# Sheet1.net
KiCad netlist of a schematic drawn in Altium Designer
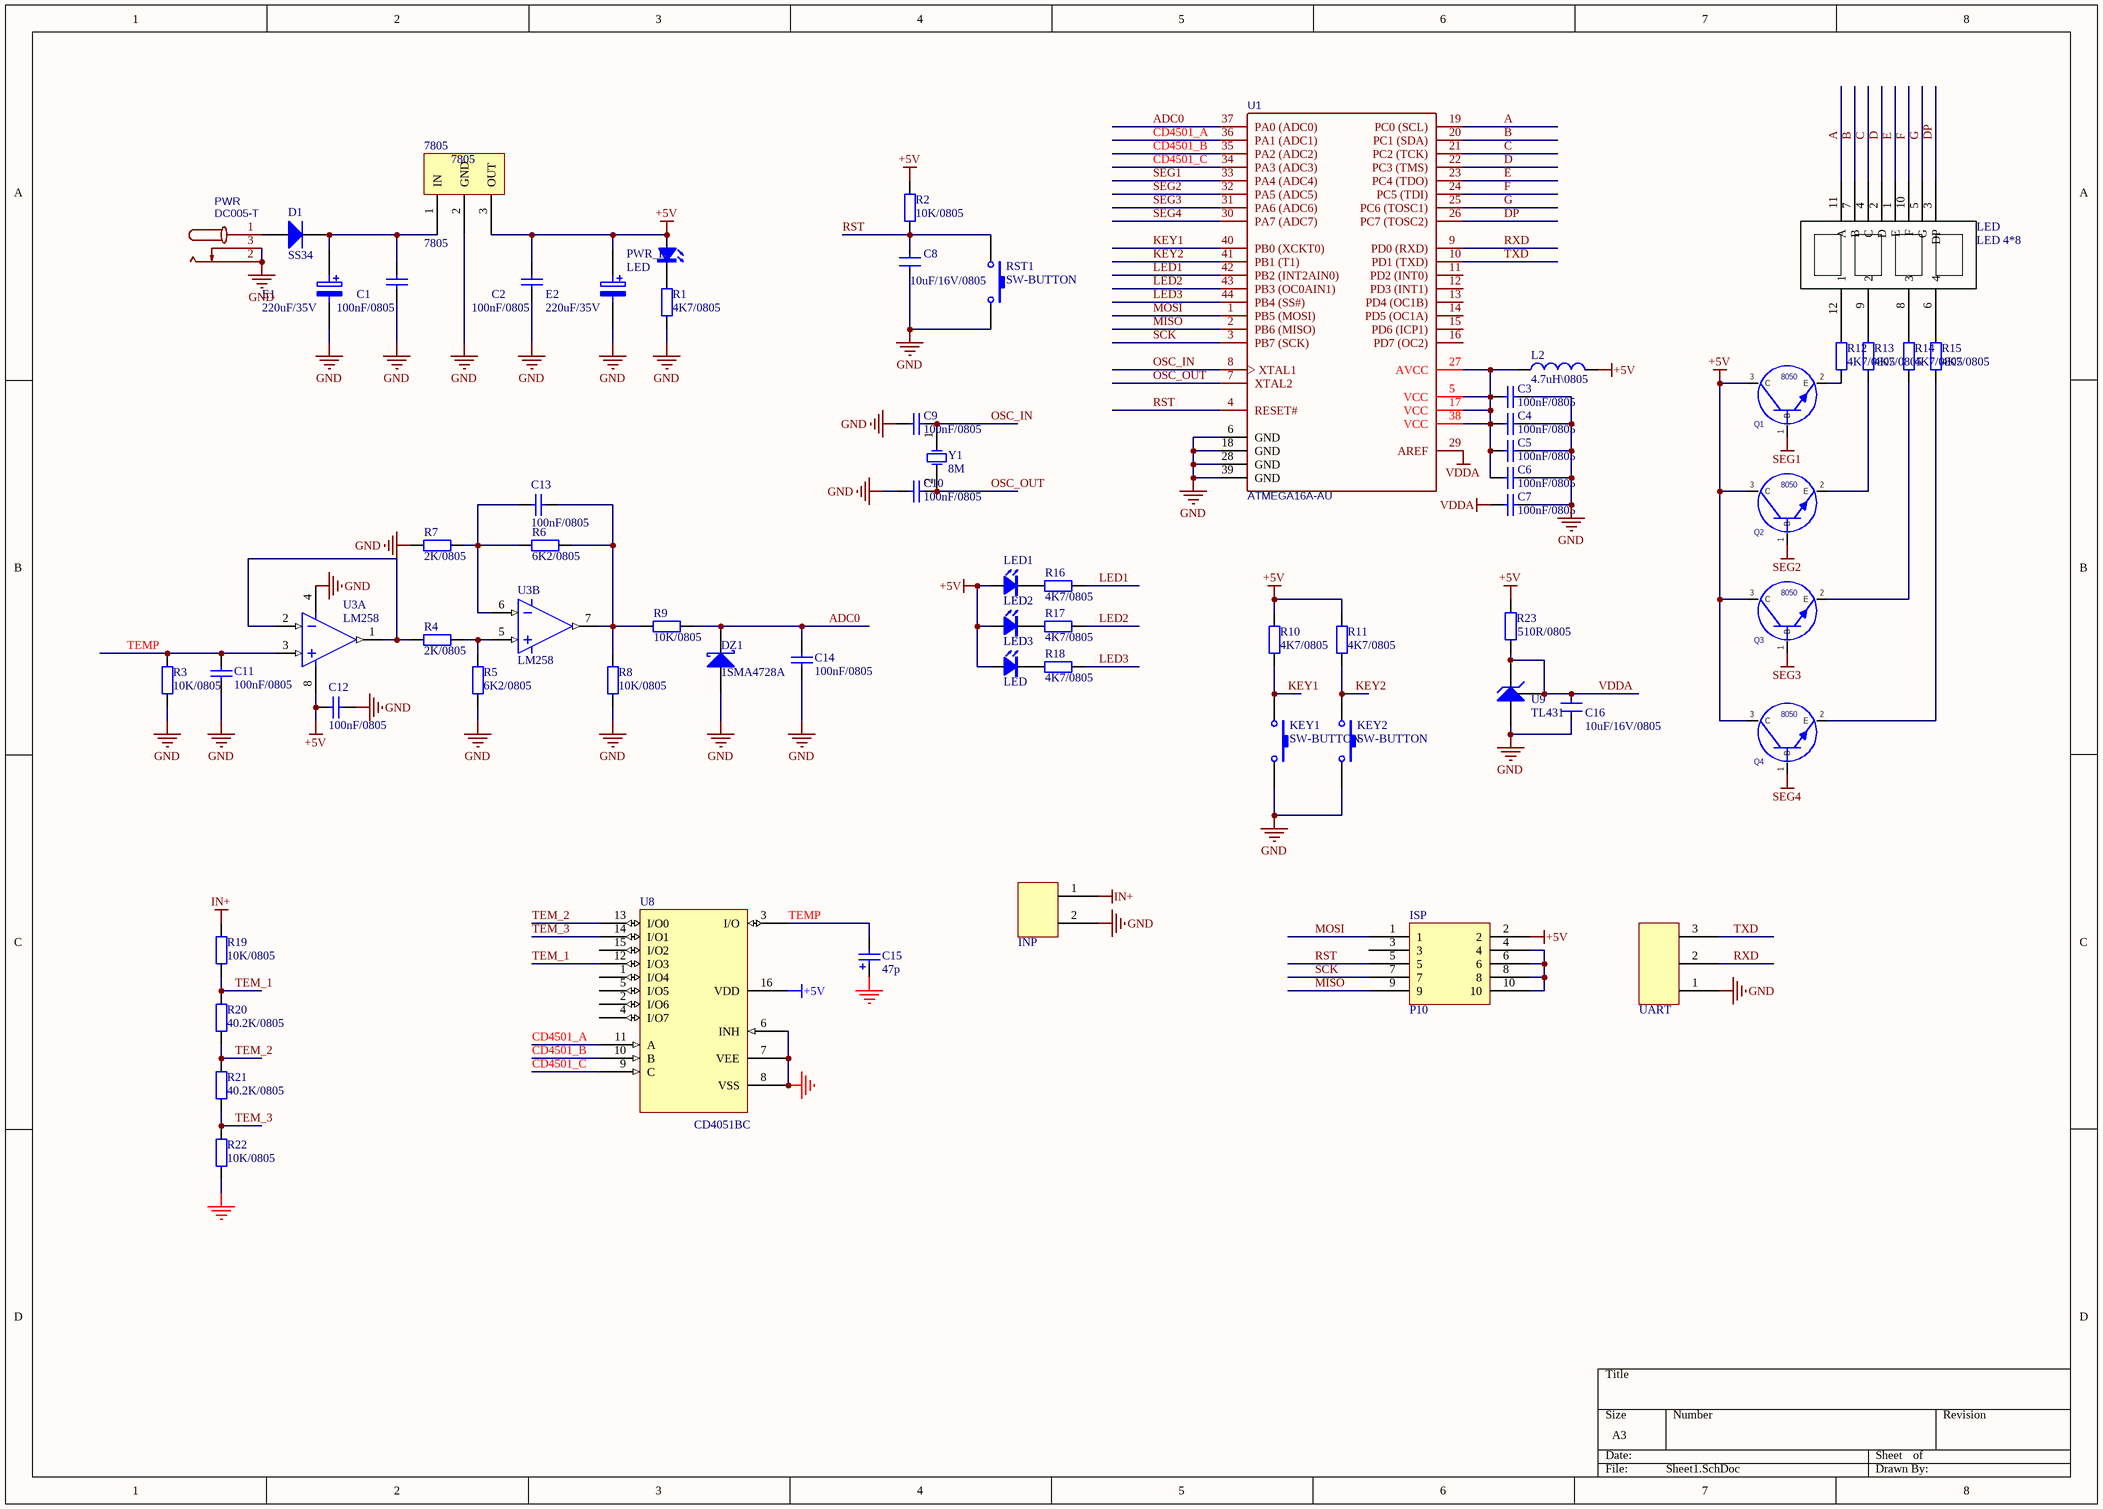
[diagram p0: Sheet1.SchDoc]

(export (version "E")
  (design (tool "Eeschema 10.0.6"))
  (components
    (comp (ref "7805") (value "7805") (footprint "7805") (libsource (lib "Schl_lib") (part "7805")))
    (comp (ref "C1")
      (value "100nF/0805")
      (footprint "C0805")
      (description "Capacitor (Semiconductor SIM Model)")
      (fields (field (name "PUBLISHER") "Altium Limited"))
      (libsource (lib "*") (part "Cap Semi"))
    )
    (comp (ref "C2")
      (value "100nF/0805")
      (footprint "C0805")
      (description "Capacitor (Semiconductor SIM Model)")
      (fields (field (name "PUBLISHER") "Altium Limited"))
      (libsource (lib "*") (part "Cap Semi"))
    )
    (comp (ref "C3")
      (value "100nF/0805")
      (footprint "C0805")
      (description "Capacitor (Semiconductor SIM Model)")
      (fields (field (name "PUBLISHER") "Altium Limited"))
      (libsource (lib "*") (part "Cap Semi"))
    )
    (comp (ref "C4")
      (value "100nF/0805")
      (footprint "C0805")
      (description "Capacitor (Semiconductor SIM Model)")
      (fields (field (name "PUBLISHER") "Altium Limited"))
      (libsource (lib "*") (part "Cap Semi"))
    )
    (comp (ref "C5")
      (value "100nF/0805")
      (footprint "C0805")
      (description "Capacitor (Semiconductor SIM Model)")
      (fields (field (name "PUBLISHER") "Altium Limited"))
      (libsource (lib "*") (part "Cap Semi"))
    )
    (comp (ref "C6")
      (value "100nF/0805")
      (footprint "C0805")
      (description "Capacitor (Semiconductor SIM Model)")
      (fields (field (name "PUBLISHER") "Altium Limited"))
      (libsource (lib "*") (part "Cap Semi"))
    )
    (comp (ref "C7")
      (value "100nF/0805")
      (footprint "C0805")
      (description "Capacitor (Semiconductor SIM Model)")
      (fields (field (name "PUBLISHER") "Altium Limited"))
      (libsource (lib "*") (part "Cap Semi"))
    )
    (comp (ref "C8")
      (value "10uF")
      (footprint "C0805")
      (description "普通小电容")
      (fields (field (name "MARK") "10uF/16V/0805"))
      (libsource (lib "MOTO_CTRL") (part "CAP"))
    )
    (comp (ref "C9")
      (value "100nF/0805")
      (footprint "C0805")
      (description "Capacitor (Semiconductor SIM Model)")
      (fields (field (name "PUBLISHER") "Altium Limited"))
      (libsource (lib "*") (part "Cap Semi"))
    )
    (comp (ref "C10")
      (value "100nF/0805")
      (footprint "C0805")
      (description "Capacitor (Semiconductor SIM Model)")
      (fields (field (name "PUBLISHER") "Altium Limited"))
      (libsource (lib "*") (part "Cap Semi"))
    )
    (comp (ref "C11")
      (value "100nF/0805")
      (footprint "C0805")
      (description "Capacitor (Semiconductor SIM Model)")
      (fields (field (name "PUBLISHER") "Altium Limited"))
      (libsource (lib "*") (part "Cap Semi"))
    )
    (comp (ref "C12")
      (value "100nF/0805")
      (footprint "C0805")
      (description "Capacitor (Semiconductor SIM Model)")
      (fields (field (name "PUBLISHER") "Altium Limited"))
      (libsource (lib "*") (part "Cap Semi"))
    )
    (comp (ref "C13")
      (value "100nF/0805")
      (footprint "C0805")
      (description "Capacitor (Semiconductor SIM Model)")
      (fields (field (name "PUBLISHER") "Altium Limited"))
      (libsource (lib "*") (part "Cap Semi"))
    )
    (comp (ref "C14")
      (value "100nF/0805")
      (footprint "C0805")
      (description "Capacitor (Semiconductor SIM Model)")
      (fields (field (name "PUBLISHER") "Altium Limited"))
      (libsource (lib "*") (part "Cap Semi"))
    )
    (comp (ref "C15")
      (value "47p")
      (footprint "C0805")
      (description "Polarized Capacitor (Radial)")
      (fields
        (field (name "MANUFACTURER") "Generic Components")
        (field (name "PUBLISHER") "Altium Hobart Technology Centre")
      )
      (libsource (lib "Miscellaneous Devices") (part "Cap Pol1"))
    )
    (comp (ref "C16")
      (value "10uF")
      (footprint "C0805")
      (description "普通小电容")
      (fields (field (name "MARK") "10uF/16V/0805"))
      (libsource (lib "SCH_Lib") (part "CAP"))
    )
    (comp (ref "D1")
      (value "SS34")
      (footprint "PCB_LIB:SMA")
      (description "High Conductance Fast Diode")
      (fields (field (name "PUBLISHER") "Altium Limited"))
      (libsource (lib "*") (part "Diode 1N914"))
    )
    (comp (ref "DZ1")
      (value "1SMA4728A")
      (footprint "PCB_LIB:SMA")
      (description "Schottky Rectifier")
      (fields (field (name "MARK") "1SMA4728A"))
      (libsource (lib "Schl_lib") (part "DZ"))
    )
    (comp (ref "E1")
      (value "220uF/35V")
      (footprint "CAP-8*10.5MM/CDVT")
      (description "Electrolytic Capacitor")
      (libsource (lib "*") (part "ELECTRO2"))
    )
    (comp (ref "E2")
      (value "220uF/35V")
      (footprint "CAP-8*10.5MM/CDVT")
      (description "Electrolytic Capacitor")
      (libsource (lib "*") (part "ELECTRO2"))
    )
    (comp (ref "INP") (value "P") (footprint "POWER2") (libsource (lib "Schl_lib") (part "P2")))
    (comp (ref "ISP") (value "P10") (footprint "IDC-10P") (libsource (lib "Schl_lib") (part "P10")))
    (comp (ref "KEY1")
      (value "SW-BUTTON")
      (footprint "KEY-SMD_4P-6-6")
      (description "6*6*5mm轻触开关")
      (libsource (lib "STC52_CAD") (part "SW-BUTTON"))
    )
    (comp (ref "KEY2")
      (value "SW-BUTTON")
      (footprint "KEY-SMD_4P-6-6")
      (description "6*6*5mm轻触开关")
      (libsource (lib "STC52_CAD") (part "SW-BUTTON"))
    )
    (comp (ref "L2")
      (value "Inductor")
      (footprint "0805L")
      (fields (field (name "MARK") "4.7u~{H}0805") (field (name "PUBLISHER") "Altium Limited"))
      (libsource (lib "Miscellaneous Devices") (part "Inductor"))
    )
    (comp (ref "LED")
      (value "LED 4*8")
      (footprint "DIGITAL_LED_0.56")
      (libsource (lib "Schl_lib") (part "LED4*8"))
    )
    (comp (ref "LED1") (value "LED") (footprint "LED0805") (libsource (lib "SCH_Lib") (part "LED")))
    (comp (ref "LED2") (value "LED") (footprint "LED0805") (libsource (lib "SCH_Lib") (part "LED")))
    (comp (ref "LED3") (value "LED") (footprint "LED0805") (libsource (lib "SCH_Lib") (part "LED")))
    (comp (ref "PWR")
      (value "DC005-T")
      (footprint "DC005")
      (fields (field (name "BOM_SUPPLIER PART") "C431532") (field (name "CONTRIBUTOR") "LCSC"))
      (libsource (lib "altium-import") (part "root_0_DC005-T_"))
    )
    (comp (ref "PWR_L") (value "LED") (footprint "LED0805") (libsource (lib "") (part "LED_1")))
    (comp (ref "Q1")
      (value "8050")
      (footprint "SOT-23")
      (description "Transistor;NPN;40V;200mA;SOT23;1.1mm;ROHS")
      (libsource (lib "*") (part "TRIODE-NPN-MMBT3904"))
    )
    (comp (ref "Q2")
      (value "8050")
      (footprint "SOT-23")
      (description "Transistor;NPN;40V;200mA;SOT23;1.1mm;ROHS")
      (libsource (lib "*") (part "TRIODE-NPN-MMBT3904"))
    )
    (comp (ref "Q3")
      (value "8050")
      (footprint "SOT-23")
      (description "Transistor;NPN;40V;200mA;SOT23;1.1mm;ROHS")
      (libsource (lib "*") (part "TRIODE-NPN-MMBT3904"))
    )
    (comp (ref "Q4")
      (value "8050")
      (footprint "SOT-23")
      (description "Transistor;NPN;40V;200mA;SOT23;1.1mm;ROHS")
      (libsource (lib "*") (part "TRIODE-NPN-MMBT3904"))
    )
    (comp (ref "R1")
      (value "4K7/0805")
      (footprint "R0805")
      (description "Resistor")
      (fields (field (name "MARK") "4K7/0805") (field (name "PUBLISHER") "Altium Limited"))
      (libsource (lib "SCH_Lib") (part "RES"))
    )
    (comp (ref "R2")
      (value "10K")
      (footprint "R0805")
      (description "Resistor")
      (fields (field (name "MARK") "10K/0805") (field (name "PUBLISHER") "Altium Limited"))
      (libsource (lib "MOTO_CTRL") (part "RES"))
    )
    (comp (ref "R3")
      (value "10K")
      (footprint "R0805")
      (description "Resistor")
      (fields (field (name "MARK") "10K/0805") (field (name "PUBLISHER") "Altium Limited"))
      (libsource (lib "MOTO_CTRL") (part "RES"))
    )
    (comp (ref "R4")
      (value "2K/0805")
      (footprint "R0805")
      (description "Resistor")
      (fields (field (name "MARK") "2K/0805") (field (name "PUBLISHER") "Altium Limited"))
      (libsource (lib "") (part "RES_1"))
    )
    (comp (ref "R5")
      (value "6K2/0805")
      (footprint "R0805")
      (description "Resistor")
      (fields (field (name "MARK") "6K2/0805") (field (name "PUBLISHER") "Altium Limited"))
      (libsource (lib "") (part "RES_2"))
    )
    (comp (ref "R6")
      (value "6K2/0805")
      (footprint "R0805")
      (description "Resistor")
      (fields (field (name "MARK") "6K2/0805") (field (name "PUBLISHER") "Altium Limited"))
      (libsource (lib "") (part "RES_3"))
    )
    (comp (ref "R7")
      (value "2K/0805")
      (footprint "R0805")
      (description "Resistor")
      (fields (field (name "MARK") "2K/0805") (field (name "PUBLISHER") "Altium Limited"))
      (libsource (lib "") (part "RES_3"))
    )
    (comp (ref "R8")
      (value "10K/0805")
      (footprint "R0805")
      (description "Resistor")
      (fields (field (name "MARK") "10K/0805") (field (name "PUBLISHER") "Altium Limited"))
      (libsource (lib "SCH_Lib") (part "RES"))
    )
    (comp (ref "R9")
      (value "10K/0805")
      (footprint "R0805")
      (description "Resistor")
      (fields (field (name "MARK") "10K/0805") (field (name "PUBLISHER") "Altium Limited"))
      (libsource (lib "") (part "RES_1"))
    )
    (comp (ref "R10")
      (value "4K7/0805")
      (footprint "R0805")
      (description "Resistor")
      (fields (field (name "MARK") "4K7/0805") (field (name "PUBLISHER") "Altium Limited"))
      (libsource (lib "") (part "RES_2"))
    )
    (comp (ref "R11")
      (value "4K7/0805")
      (footprint "R0805")
      (description "Resistor")
      (fields (field (name "MARK") "4K7/0805") (field (name "PUBLISHER") "Altium Limited"))
      (libsource (lib "") (part "RES_2"))
    )
    (comp (ref "R12")
      (value "4K7/0805")
      (footprint "R0805")
      (description "Resistor")
      (fields (field (name "MARK") "4K7/0805") (field (name "PUBLISHER") "Altium Limited"))
      (libsource (lib "") (part "RES_2"))
    )
    (comp (ref "R13")
      (value "4K7/0805")
      (footprint "R0805")
      (description "Resistor")
      (fields (field (name "MARK") "4K7/0805") (field (name "PUBLISHER") "Altium Limited"))
      (libsource (lib "") (part "RES_2"))
    )
    (comp (ref "R14")
      (value "4K7/0805")
      (footprint "R0805")
      (description "Resistor")
      (fields (field (name "MARK") "4K7/0805") (field (name "PUBLISHER") "Altium Limited"))
      (libsource (lib "") (part "RES_2"))
    )
    (comp (ref "R15")
      (value "4K7/0805")
      (footprint "R0805")
      (description "Resistor")
      (fields (field (name "MARK") "4K7/0805") (field (name "PUBLISHER") "Altium Limited"))
      (libsource (lib "") (part "RES_2"))
    )
    (comp (ref "R16")
      (value "4K7/0805")
      (footprint "R0805")
      (description "Resistor")
      (fields (field (name "MARK") "4K7/0805") (field (name "PUBLISHER") "Altium Limited"))
      (libsource (lib "") (part "RES_1"))
    )
    (comp (ref "R17")
      (value "4K7/0805")
      (footprint "R0805")
      (description "Resistor")
      (fields (field (name "MARK") "4K7/0805") (field (name "PUBLISHER") "Altium Limited"))
      (libsource (lib "") (part "RES_1"))
    )
    (comp (ref "R18")
      (value "4K7/0805")
      (footprint "R0805")
      (description "Resistor")
      (fields (field (name "MARK") "4K7/0805") (field (name "PUBLISHER") "Altium Limited"))
      (libsource (lib "") (part "RES_1"))
    )
    (comp (ref "R19")
      (value "10K/0805")
      (footprint "R0805")
      (description "Resistor")
      (fields (field (name "MARK") "10K/0805") (field (name "PUBLISHER") "Altium Limited"))
      (libsource (lib "") (part "RES_2"))
    )
    (comp (ref "R20")
      (value "40.2K/0805")
      (footprint "R0805")
      (description "Resistor")
      (fields (field (name "MARK") "40.2K/0805") (field (name "PUBLISHER") "Altium Limited"))
      (libsource (lib "") (part "RES_2"))
    )
    (comp (ref "R21")
      (value "40.2K/0805")
      (footprint "R0805")
      (description "Resistor")
      (fields (field (name "MARK") "40.2K/0805") (field (name "PUBLISHER") "Altium Limited"))
      (libsource (lib "") (part "RES_2"))
    )
    (comp (ref "R22")
      (value "10K/0805")
      (footprint "R0805")
      (description "Resistor")
      (fields (field (name "MARK") "10K/0805") (field (name "PUBLISHER") "Altium Limited"))
      (libsource (lib "") (part "RES_2"))
    )
    (comp (ref "R23")
      (value "510R")
      (footprint "R0805")
      (description "Resistor")
      (fields (field (name "MARK") "510R/0805") (field (name "PUBLISHER") "Altium Limited"))
      (libsource (lib "") (part "RES_2"))
    )
    (comp (ref "RST1")
      (value "SW-BUTTON")
      (footprint "KEY-SMD_4P-6-6")
      (description "6*6*5mm轻触开关")
      (libsource (lib "STC52_CAD") (part "SW-BUTTON"))
    )
    (comp (ref "U1")
      (value "ATMEGA16A-AU")
      (footprint "TQFP-44")
      (fields (field (name "BOM_SUPPLIER PART") "C5658"))
      (libsource (lib "Schl_lib") (part "ATMEGA16A-AU"))
    )
    (comp (ref "U3")
      (value "LM258")
      (footprint "SO-8")
      (description "电压比较器")
      (libsource (lib "SCH_Lib") (part "LM393"))
    )
    (comp (ref "U8") (value "CD4051BC") (footprint "SO-16") (libsource (lib "*") (part "CD4051BC")))
    (comp (ref "U9")
      (value "TL431")
      (footprint "TL431")
      (fields (field (name "MARK") "TL431") (field (name "PUBLISHER") "Altium Limited"))
      (libsource (lib "Schl_lib") (part "TL431"))
    )
    (comp (ref "UART") (value "P") (footprint "POWER3") (libsource (lib "Schl_lib") (part "P3")))
    (comp (ref "Y1")
      (value "8M")
      (footprint "SMD3225")
      (description "Crystal Oscillator")
      (fields (field (name "PUBLISHER") "Altium Limited"))
      (libsource (lib "Miscellaneous Devices") (part "XTAL"))
    )
  )
  (nets
    (net (code "1") (name "+5V") (class "Default")
      (node (ref "7805") (pin "3") (pinfunction "OUT_3") (pintype "passive"))
      (node (ref "C12") (pin "1") (pinfunction "1_1") (pintype "passive"))
      (node (ref "C2") (pin "2") (pinfunction "2_2") (pintype "passive"))
      (node (ref "E2") (pin "1") (pinfunction "1_1") (pintype "passive"))
      (node (ref "ISP") (pin "2") (pinfunction "2_2") (pintype "passive"))
      (node (ref "L2") (pin "2") (pinfunction "2_2") (pintype "passive"))
      (node (ref "LED1") (pin "1") (pinfunction "A_1") (pintype "passive"))
      (node (ref "LED2") (pin "1") (pinfunction "A_1") (pintype "passive"))
      (node (ref "LED3") (pin "1") (pinfunction "A_1") (pintype "passive"))
      (node (ref "PWR_L") (pin "1") (pinfunction "A_1") (pintype "passive"))
      (node (ref "Q1") (pin "3") (pinfunction "C_3") (pintype "passive"))
      (node (ref "Q2") (pin "3") (pinfunction "C_3") (pintype "passive"))
      (node (ref "Q3") (pin "3") (pinfunction "C_3") (pintype "passive"))
      (node (ref "Q4") (pin "3") (pinfunction "C_3") (pintype "passive"))
      (node (ref "R10") (pin "2") (pinfunction "2_2") (pintype "passive"))
      (node (ref "R11") (pin "2") (pinfunction "2_2") (pintype "passive"))
      (node (ref "R2") (pin "2") (pinfunction "2_2") (pintype "passive"))
      (node (ref "R23") (pin "2") (pinfunction "2_2") (pintype "passive"))
      (node (ref "U3") (pin "8") (pinfunction "V+_8") (pintype "power_in"))
      (node (ref "U8") (pin "16") (pinfunction "VDD_16") (pintype "power_in"))
    )
    (net (code "2") (name "/A") (class "Default")
      (node (ref "LED") (pin "11") (pinfunction "A_11") (pintype "passive"))
      (node (ref "U1") (pin "19") (pinfunction "PC0_(SCL)_19") (pintype "passive"))
    )
    (net (code "3") (name "/ADC0") (class "Default")
      (node (ref "C14") (pin "1") (pinfunction "1_1") (pintype "passive"))
      (node (ref "DZ1") (pin "2") (pinfunction "K_2") (pintype "passive"))
      (node (ref "R9") (pin "2") (pinfunction "2_2") (pintype "passive"))
      (node (ref "U1") (pin "37") (pinfunction "PA0_(ADC0)_37") (pintype "passive"))
    )
    (net (code "4") (name "/B") (class "Default")
      (node (ref "LED") (pin "7") (pinfunction "B_7") (pintype "passive"))
      (node (ref "U1") (pin "20") (pinfunction "PC1_(SDA)_20") (pintype "passive"))
    )
    (net (code "5") (name "/C") (class "Default")
      (node (ref "LED") (pin "4") (pinfunction "C_4") (pintype "passive"))
      (node (ref "U1") (pin "21") (pinfunction "PC2_(TCK)_21") (pintype "passive"))
    )
    (net (code "6") (name "/CD4501_A") (class "Default")
      (node (ref "U1") (pin "36") (pinfunction "PA1_(ADC1)_36") (pintype "passive"))
      (node (ref "U8") (pin "11") (pinfunction "A_11") (pintype "input"))
    )
    (net (code "7") (name "/CD4501_B") (class "Default")
      (node (ref "U1") (pin "35") (pinfunction "PA2_(ADC2)_35") (pintype "passive"))
      (node (ref "U8") (pin "10") (pinfunction "B_10") (pintype "input"))
    )
    (net (code "8") (name "/CD4501_C") (class "Default")
      (node (ref "U1") (pin "34") (pinfunction "PA3_(ADC3)_34") (pintype "passive"))
      (node (ref "U8") (pin "9") (pinfunction "C_9") (pintype "input"))
    )
    (net (code "9") (name "/D") (class "Default")
      (node (ref "LED") (pin "2") (pinfunction "D_2") (pintype "passive"))
      (node (ref "U1") (pin "22") (pinfunction "PC3_(TMS)_22") (pintype "passive"))
    )
    (net (code "10") (name "/DP") (class "Default")
      (node (ref "LED") (pin "3") (pinfunction "DP_3") (pintype "passive"))
      (node (ref "U1") (pin "26") (pinfunction "PC7_(TOSC2)_26") (pintype "passive"))
    )
    (net (code "11") (name "/E") (class "Default")
      (node (ref "LED") (pin "1") (pinfunction "E_1") (pintype "passive"))
      (node (ref "U1") (pin "23") (pinfunction "PC4_(TDO)_23") (pintype "passive"))
    )
    (net (code "12") (name "/F") (class "Default")
      (node (ref "LED") (pin "10") (pinfunction "F_10") (pintype "passive"))
      (node (ref "U1") (pin "24") (pinfunction "PC5_(TDI)_24") (pintype "passive"))
    )
    (net (code "13") (name "/G") (class "Default")
      (node (ref "LED") (pin "5") (pinfunction "G_5") (pintype "passive"))
      (node (ref "U1") (pin "25") (pinfunction "PC6_(TOSC1)_25") (pintype "passive"))
    )
    (net (code "14") (name "/KEY1") (class "Default")
      (node (ref "KEY1") (pin "1") (pinfunction "1_1") (pintype "passive"))
      (node (ref "R10") (pin "1") (pinfunction "1_1") (pintype "passive"))
      (node (ref "U1") (pin "40") (pinfunction "PB0_(XCKT0)_40") (pintype "passive"))
    )
    (net (code "15") (name "/KEY2") (class "Default")
      (node (ref "KEY2") (pin "1") (pinfunction "1_1") (pintype "passive"))
      (node (ref "R11") (pin "1") (pinfunction "1_1") (pintype "passive"))
      (node (ref "U1") (pin "41") (pinfunction "PB1_(T1)_41") (pintype "passive"))
    )
    (net (code "16") (name "/LED1") (class "Default")
      (node (ref "R16") (pin "2") (pinfunction "2_2") (pintype "passive"))
      (node (ref "U1") (pin "42") (pinfunction "PB2_(INT2AIN0)_42") (pintype "passive"))
    )
    (net (code "17") (name "/LED2") (class "Default")
      (node (ref "R17") (pin "2") (pinfunction "2_2") (pintype "passive"))
      (node (ref "U1") (pin "43") (pinfunction "PB3_(OC0AIN1)_43") (pintype "passive"))
    )
    (net (code "18") (name "/LED3") (class "Default")
      (node (ref "R18") (pin "2") (pinfunction "2_2") (pintype "passive"))
      (node (ref "U1") (pin "44") (pinfunction "PB4_(SS#)_44") (pintype "passive"))
    )
    (net (code "19") (name "/MISO") (class "Default")
      (node (ref "ISP") (pin "9") (pinfunction "9_9") (pintype "passive"))
      (node (ref "U1") (pin "2") (pinfunction "PB6_(MISO)_2") (pintype "passive"))
    )
    (net (code "20") (name "/MOSI") (class "Default")
      (node (ref "ISP") (pin "1") (pinfunction "1_1") (pintype "passive"))
      (node (ref "U1") (pin "1") (pinfunction "PB5_(MOSI)_1") (pintype "passive"))
    )
    (net (code "21") (name "/OSC_IN") (class "Default")
      (node (ref "C9") (pin "2") (pinfunction "2_2") (pintype "passive"))
      (node (ref "U1") (pin "8") (pinfunction "XTAL1_8") (pintype "passive"))
      (node (ref "Y1") (pin "1") (pinfunction "OSC1_1") (pintype "passive"))
    )
    (net (code "22") (name "/OSC_OUT") (class "Default")
      (node (ref "C10") (pin "2") (pinfunction "2_2") (pintype "passive"))
      (node (ref "U1") (pin "7") (pinfunction "XTAL2_7") (pintype "passive"))
      (node (ref "Y1") (pin "2") (pinfunction "OSC2_2") (pintype "passive"))
    )
    (net (code "23") (name "/RST") (class "Default")
      (node (ref "C8") (pin "1") (pinfunction "1_1") (pintype "passive"))
      (node (ref "ISP") (pin "5") (pinfunction "5_5") (pintype "passive"))
      (node (ref "R2") (pin "1") (pinfunction "1_1") (pintype "passive"))
      (node (ref "RST1") (pin "1") (pinfunction "1_1") (pintype "passive"))
      (node (ref "U1") (pin "4") (pinfunction "RESET#_4") (pintype "passive"))
    )
    (net (code "24") (name "/RXD") (class "Default")
      (node (ref "U1") (pin "9") (pinfunction "PD0_(RXD)_9") (pintype "passive"))
      (node (ref "UART") (pin "2") (pintype "passive"))
    )
    (net (code "25") (name "/SCK") (class "Default")
      (node (ref "ISP") (pin "7") (pinfunction "7_7") (pintype "passive"))
      (node (ref "U1") (pin "3") (pinfunction "PB7_(SCK)_3") (pintype "passive"))
    )
    (net (code "26") (name "/TEMP") (class "Default")
      (node (ref "C11") (pin "2") (pinfunction "2_2") (pintype "passive"))
      (node (ref "C15") (pin "2") (pinfunction "2_2") (pintype "passive"))
      (node (ref "R3") (pin "2") (pinfunction "2_2") (pintype "passive"))
      (node (ref "U3") (pin "3") (pinfunction "+INA_3") (pintype "input"))
      (node (ref "U8") (pin "3") (pinfunction "I/O_3") (pintype "bidirectional"))
    )
    (net (code "27") (name "/TEM_1") (class "Default")
      (node (ref "R19") (pin "1") (pinfunction "1_1") (pintype "passive"))
      (node (ref "R20") (pin "2") (pinfunction "2_2") (pintype "passive"))
      (node (ref "U8") (pin "12") (pinfunction "I/O3_12") (pintype "bidirectional"))
    )
    (net (code "28") (name "/TEM_2") (class "Default")
      (node (ref "R20") (pin "1") (pinfunction "1_1") (pintype "passive"))
      (node (ref "R21") (pin "2") (pinfunction "2_2") (pintype "passive"))
      (node (ref "U8") (pin "13") (pinfunction "I/O0_13") (pintype "bidirectional"))
    )
    (net (code "29") (name "/TEM_3") (class "Default")
      (node (ref "R21") (pin "1") (pinfunction "1_1") (pintype "passive"))
      (node (ref "R22") (pin "2") (pinfunction "2_2") (pintype "passive"))
      (node (ref "U8") (pin "14") (pinfunction "I/O1_14") (pintype "bidirectional"))
    )
    (net (code "30") (name "/TXD") (class "Default")
      (node (ref "U1") (pin "10") (pinfunction "PD1_(TXD)_10") (pintype "passive"))
      (node (ref "UART") (pin "3") (pintype "passive"))
    )
    (net (code "31") (name "GND") (class "Default")
      (node (ref "7805") (pin "2") (pinfunction "GND_2") (pintype "passive"))
      (node (ref "C1") (pin "1") (pinfunction "1_1") (pintype "passive"))
      (node (ref "C10") (pin "1") (pinfunction "1_1") (pintype "passive"))
      (node (ref "C11") (pin "1") (pinfunction "1_1") (pintype "passive"))
      (node (ref "C12") (pin "2") (pinfunction "2_2") (pintype "passive"))
      (node (ref "C14") (pin "2") (pinfunction "2_2") (pintype "passive"))
      (node (ref "C15") (pin "1") (pinfunction "1_1") (pintype "passive"))
      (node (ref "C16") (pin "2") (pinfunction "2_2") (pintype "passive"))
      (node (ref "C2") (pin "1") (pinfunction "1_1") (pintype "passive"))
      (node (ref "C3") (pin "2") (pinfunction "2_2") (pintype "passive"))
      (node (ref "C4") (pin "2") (pinfunction "2_2") (pintype "passive"))
      (node (ref "C5") (pin "2") (pinfunction "2_2") (pintype "passive"))
      (node (ref "C6") (pin "2") (pinfunction "2_2") (pintype "passive"))
      (node (ref "C7") (pin "2") (pinfunction "2_2") (pintype "passive"))
      (node (ref "C8") (pin "2") (pinfunction "2_2") (pintype "passive"))
      (node (ref "C9") (pin "1") (pinfunction "1_1") (pintype "passive"))
      (node (ref "DZ1") (pin "1") (pinfunction "A_1") (pintype "passive"))
      (node (ref "E1") (pin "2") (pinfunction "2_2") (pintype "passive"))
      (node (ref "E2") (pin "2") (pinfunction "2_2") (pintype "passive"))
      (node (ref "INP") (pin "2") (pintype "passive"))
      (node (ref "KEY1") (pin "2") (pinfunction "2_2") (pintype "passive"))
      (node (ref "KEY2") (pin "2") (pinfunction "2_2") (pintype "passive"))
      (node (ref "PWR") (pin "2") (pinfunction "2_2") (pintype "passive"))
      (node (ref "PWR") (pin "3") (pinfunction "3_3") (pintype "passive"))
      (node (ref "R1") (pin "2") (pinfunction "2_2") (pintype "passive"))
      (node (ref "R22") (pin "1") (pinfunction "1_1") (pintype "passive"))
      (node (ref "R3") (pin "1") (pinfunction "1_1") (pintype "passive"))
      (node (ref "R5") (pin "1") (pinfunction "1_1") (pintype "passive"))
      (node (ref "R7") (pin "2") (pinfunction "2_2") (pintype "passive"))
      (node (ref "R8") (pin "2") (pinfunction "2_2") (pintype "passive"))
      (node (ref "RST1") (pin "2") (pinfunction "2_2") (pintype "passive"))
      (node (ref "U1") (pin "18") (pinfunction "GND_18") (pintype "passive"))
      (node (ref "U1") (pin "28") (pinfunction "GND_28") (pintype "passive"))
      (node (ref "U1") (pin "39") (pinfunction "GND_39") (pintype "passive"))
      (node (ref "U1") (pin "6") (pinfunction "GND_6") (pintype "passive"))
      (node (ref "U3") (pin "4") (pinfunction "V-_4") (pintype "power_in"))
      (node (ref "U8") (pin "6") (pinfunction "INH_6") (pintype "input"))
      (node (ref "U8") (pin "7") (pinfunction "VEE_7") (pintype "power_in"))
      (node (ref "U8") (pin "8") (pinfunction "VSS_8") (pintype "power_in"))
      (node (ref "U9") (pin "3") (pinfunction "ANO_3") (pintype "passive"))
      (node (ref "UART") (pin "1") (pintype "passive"))
    )
    (net (code "32") (name "IN+") (class "Default")
      (node (ref "INP") (pin "1") (pintype "passive"))
      (node (ref "R19") (pin "2") (pinfunction "2_2") (pintype "passive"))
    )
    (net (code "33") (name "Net-(7805-IN)") (class "Default")
      (node (ref "7805") (pin "1") (pinfunction "IN_1") (pintype "passive"))
      (node (ref "C1") (pin "2") (pinfunction "2_2") (pintype "passive"))
      (node (ref "D1") (pin "2") (pinfunction "K_2") (pintype "passive"))
      (node (ref "E1") (pin "1") (pinfunction "1_1") (pintype "passive"))
    )
    (net (code "34") (name "Net-(D1-A)") (class "Default")
      (node (ref "D1") (pin "1") (pinfunction "A_1") (pintype "passive"))
      (node (ref "PWR") (pin "1") (pinfunction "1_1") (pintype "passive"))
    )
    (net (code "35") (name "Net-(ISP-Pad10)") (class "Default")
      (node (ref "ISP") (pin "10") (pinfunction "10_10") (pintype "passive"))
      (node (ref "ISP") (pin "4") (pinfunction "4_4") (pintype "passive"))
      (node (ref "ISP") (pin "6") (pinfunction "6_6") (pintype "passive"))
      (node (ref "ISP") (pin "8") (pinfunction "8_8") (pintype "passive"))
    )
    (net (code "36") (name "Net-(LED-1)") (class "Default")
      (node (ref "LED") (pin "12") (pinfunction "1_12") (pintype "passive"))
      (node (ref "R12") (pin "2") (pinfunction "2_2") (pintype "passive"))
    )
    (net (code "37") (name "Net-(LED-2)") (class "Default")
      (node (ref "LED") (pin "9") (pinfunction "2_9") (pintype "passive"))
      (node (ref "R13") (pin "2") (pinfunction "2_2") (pintype "passive"))
    )
    (net (code "38") (name "Net-(LED-3)") (class "Default")
      (node (ref "LED") (pin "8") (pinfunction "3_8") (pintype "passive"))
      (node (ref "R14") (pin "2") (pinfunction "2_2") (pintype "passive"))
    )
    (net (code "39") (name "Net-(LED-4)") (class "Default")
      (node (ref "LED") (pin "6") (pinfunction "4_6") (pintype "passive"))
      (node (ref "R15") (pin "2") (pinfunction "2_2") (pintype "passive"))
    )
    (net (code "40") (name "Net-(LED1-K)") (class "Default")
      (node (ref "LED1") (pin "2") (pinfunction "K_2") (pintype "passive"))
      (node (ref "R16") (pin "1") (pinfunction "1_1") (pintype "passive"))
    )
    (net (code "41") (name "Net-(LED2-K)") (class "Default")
      (node (ref "LED2") (pin "2") (pinfunction "K_2") (pintype "passive"))
      (node (ref "R17") (pin "1") (pinfunction "1_1") (pintype "passive"))
    )
    (net (code "42") (name "Net-(LED3-K)") (class "Default")
      (node (ref "LED3") (pin "2") (pinfunction "K_2") (pintype "passive"))
      (node (ref "R18") (pin "1") (pinfunction "1_1") (pintype "passive"))
    )
    (net (code "43") (name "Net-(PWR_L-K)") (class "Default")
      (node (ref "PWR_L") (pin "2") (pinfunction "K_2") (pintype "passive"))
      (node (ref "R1") (pin "1") (pinfunction "1_1") (pintype "passive"))
    )
    (net (code "44") (name "Net-(Q1-E)") (class "Default")
      (node (ref "Q1") (pin "2") (pinfunction "E_2") (pintype "passive"))
      (node (ref "R12") (pin "1") (pinfunction "1_1") (pintype "passive"))
    )
    (net (code "45") (name "Net-(Q2-E)") (class "Default")
      (node (ref "Q2") (pin "2") (pinfunction "E_2") (pintype "passive"))
      (node (ref "R13") (pin "1") (pinfunction "1_1") (pintype "passive"))
    )
    (net (code "46") (name "Net-(Q3-E)") (class "Default")
      (node (ref "Q3") (pin "2") (pinfunction "E_2") (pintype "passive"))
      (node (ref "R14") (pin "1") (pinfunction "1_1") (pintype "passive"))
    )
    (net (code "47") (name "Net-(Q4-E)") (class "Default")
      (node (ref "Q4") (pin "2") (pinfunction "E_2") (pintype "passive"))
      (node (ref "R15") (pin "1") (pinfunction "1_1") (pintype "passive"))
    )
    (net (code "48") (name "Net-(U1-AVCC)") (class "Default")
      (node (ref "C3") (pin "1") (pinfunction "1_1") (pintype "passive"))
      (node (ref "C4") (pin "1") (pinfunction "1_1") (pintype "passive"))
      (node (ref "C5") (pin "1") (pinfunction "1_1") (pintype "passive"))
      (node (ref "C6") (pin "1") (pinfunction "1_1") (pintype "passive"))
      (node (ref "L2") (pin "1") (pinfunction "1_1") (pintype "passive"))
      (node (ref "U1") (pin "17") (pinfunction "VCC_17") (pintype "passive"))
      (node (ref "U1") (pin "27") (pinfunction "AVCC_27") (pintype "passive"))
      (node (ref "U1") (pin "38") (pinfunction "VCC_38") (pintype "passive"))
      (node (ref "U1") (pin "5") (pinfunction "VCC_5") (pintype "passive"))
    )
    (net (code "49") (name "Net-(U3A--INA)") (class "Default")
      (node (ref "R4") (pin "1") (pinfunction "1_1") (pintype "passive"))
      (node (ref "U3") (pin "1") (pinfunction "OUTA_1") (pintype "output"))
      (node (ref "U3") (pin "2") (pinfunction "-INA_2") (pintype "input"))
    )
    (net (code "50") (name "Net-(U3B-+INB)") (class "Default")
      (node (ref "R4") (pin "2") (pinfunction "2_2") (pintype "passive"))
      (node (ref "R5") (pin "2") (pinfunction "2_2") (pintype "passive"))
      (node (ref "U3") (pin "5") (pinfunction "+INB_5") (pintype "input"))
    )
    (net (code "51") (name "Net-(U3B--INB)") (class "Default")
      (node (ref "C13") (pin "1") (pinfunction "1_1") (pintype "passive"))
      (node (ref "R6") (pin "2") (pinfunction "2_2") (pintype "passive"))
      (node (ref "R7") (pin "1") (pinfunction "1_1") (pintype "passive"))
      (node (ref "U3") (pin "6") (pinfunction "-INB_6") (pintype "input"))
    )
    (net (code "52") (name "Net-(U3B-OUTB)") (class "Default")
      (node (ref "C13") (pin "2") (pinfunction "2_2") (pintype "passive"))
      (node (ref "R6") (pin "1") (pinfunction "1_1") (pintype "passive"))
      (node (ref "R8") (pin "1") (pinfunction "1_1") (pintype "passive"))
      (node (ref "R9") (pin "1") (pinfunction "1_1") (pintype "passive"))
      (node (ref "U3") (pin "7") (pinfunction "OUTB_7") (pintype "output"))
    )
    (net (code "53") (name "SEG1") (class "Default")
      (node (ref "Q1") (pin "1") (pinfunction "B_1") (pintype "passive"))
      (node (ref "U1") (pin "33") (pinfunction "PA4_(ADC4)_33") (pintype "passive"))
    )
    (net (code "54") (name "SEG2") (class "Default")
      (node (ref "Q2") (pin "1") (pinfunction "B_1") (pintype "passive"))
      (node (ref "U1") (pin "32") (pinfunction "PA5_(ADC5)_32") (pintype "passive"))
    )
    (net (code "55") (name "SEG3") (class "Default")
      (node (ref "Q3") (pin "1") (pinfunction "B_1") (pintype "passive"))
      (node (ref "U1") (pin "31") (pinfunction "PA6_(ADC6)_31") (pintype "passive"))
    )
    (net (code "56") (name "SEG4") (class "Default")
      (node (ref "Q4") (pin "1") (pinfunction "B_1") (pintype "passive"))
      (node (ref "U1") (pin "30") (pinfunction "PA7_(ADC7)_30") (pintype "passive"))
    )
    (net (code "57") (name "VDDA") (class "Default")
      (node (ref "C16") (pin "1") (pinfunction "1_1") (pintype "passive"))
      (node (ref "C7") (pin "1") (pinfunction "1_1") (pintype "passive"))
      (node (ref "R23") (pin "1") (pinfunction "1_1") (pintype "passive"))
      (node (ref "U1") (pin "29") (pinfunction "AREF_29") (pintype "passive"))
      (node (ref "U9") (pin "1") (pinfunction "CAT_1") (pintype "passive"))
      (node (ref "U9") (pin "2") (pinfunction "REF_2") (pintype "passive"))
    )
    (net (code "58") (name "unconnected-(ISP-Pad3)") (class "Default")
      (node (ref "ISP") (pin "3") (pinfunction "3_3") (pintype "passive"))
    )
    (net (code "59") (name "unconnected-(U1-PD2_(INT0)-Pad11)") (class "Default")
      (node (ref "U1") (pin "11") (pinfunction "PD2_(INT0)_11") (pintype "passive"))
    )
    (net (code "60") (name "unconnected-(U1-PD3_(INT1)-Pad12)") (class "Default")
      (node (ref "U1") (pin "12") (pinfunction "PD3_(INT1)_12") (pintype "passive"))
    )
    (net (code "61") (name "unconnected-(U1-PD4_(OC1B)-Pad13)") (class "Default")
      (node (ref "U1") (pin "13") (pinfunction "PD4_(OC1B)_13") (pintype "passive"))
    )
    (net (code "62") (name "unconnected-(U1-PD5_(OC1A)-Pad14)") (class "Default")
      (node (ref "U1") (pin "14") (pinfunction "PD5_(OC1A)_14") (pintype "passive"))
    )
    (net (code "63") (name "unconnected-(U1-PD6_(ICP1)-Pad15)") (class "Default")
      (node (ref "U1") (pin "15") (pinfunction "PD6_(ICP1)_15") (pintype "passive"))
    )
    (net (code "64") (name "unconnected-(U1-PD7_(OC2)-Pad16)") (class "Default")
      (node (ref "U1") (pin "16") (pinfunction "PD7_(OC2)_16") (pintype "passive"))
    )
    (net (code "65") (name "unconnected-(U8-I{slash}O2-Pad15)") (class "Default")
      (node (ref "U8") (pin "15") (pinfunction "I/O2_15") (pintype "bidirectional"))
    )
    (net (code "66") (name "unconnected-(U8-I{slash}O4-Pad1)") (class "Default")
      (node (ref "U8") (pin "1") (pinfunction "I/O4_1") (pintype "bidirectional"))
    )
    (net (code "67") (name "unconnected-(U8-I{slash}O5-Pad5)") (class "Default")
      (node (ref "U8") (pin "5") (pinfunction "I/O5_5") (pintype "bidirectional"))
    )
    (net (code "68") (name "unconnected-(U8-I{slash}O6-Pad2)") (class "Default")
      (node (ref "U8") (pin "2") (pinfunction "I/O6_2") (pintype "bidirectional"))
    )
    (net (code "69") (name "unconnected-(U8-I{slash}O7-Pad4)") (class "Default")
      (node (ref "U8") (pin "4") (pinfunction "I/O7_4") (pintype "bidirectional"))
    )
  )
)
